# beechainuino.net
KiCad netlist of a schematic drawn in EAGLE
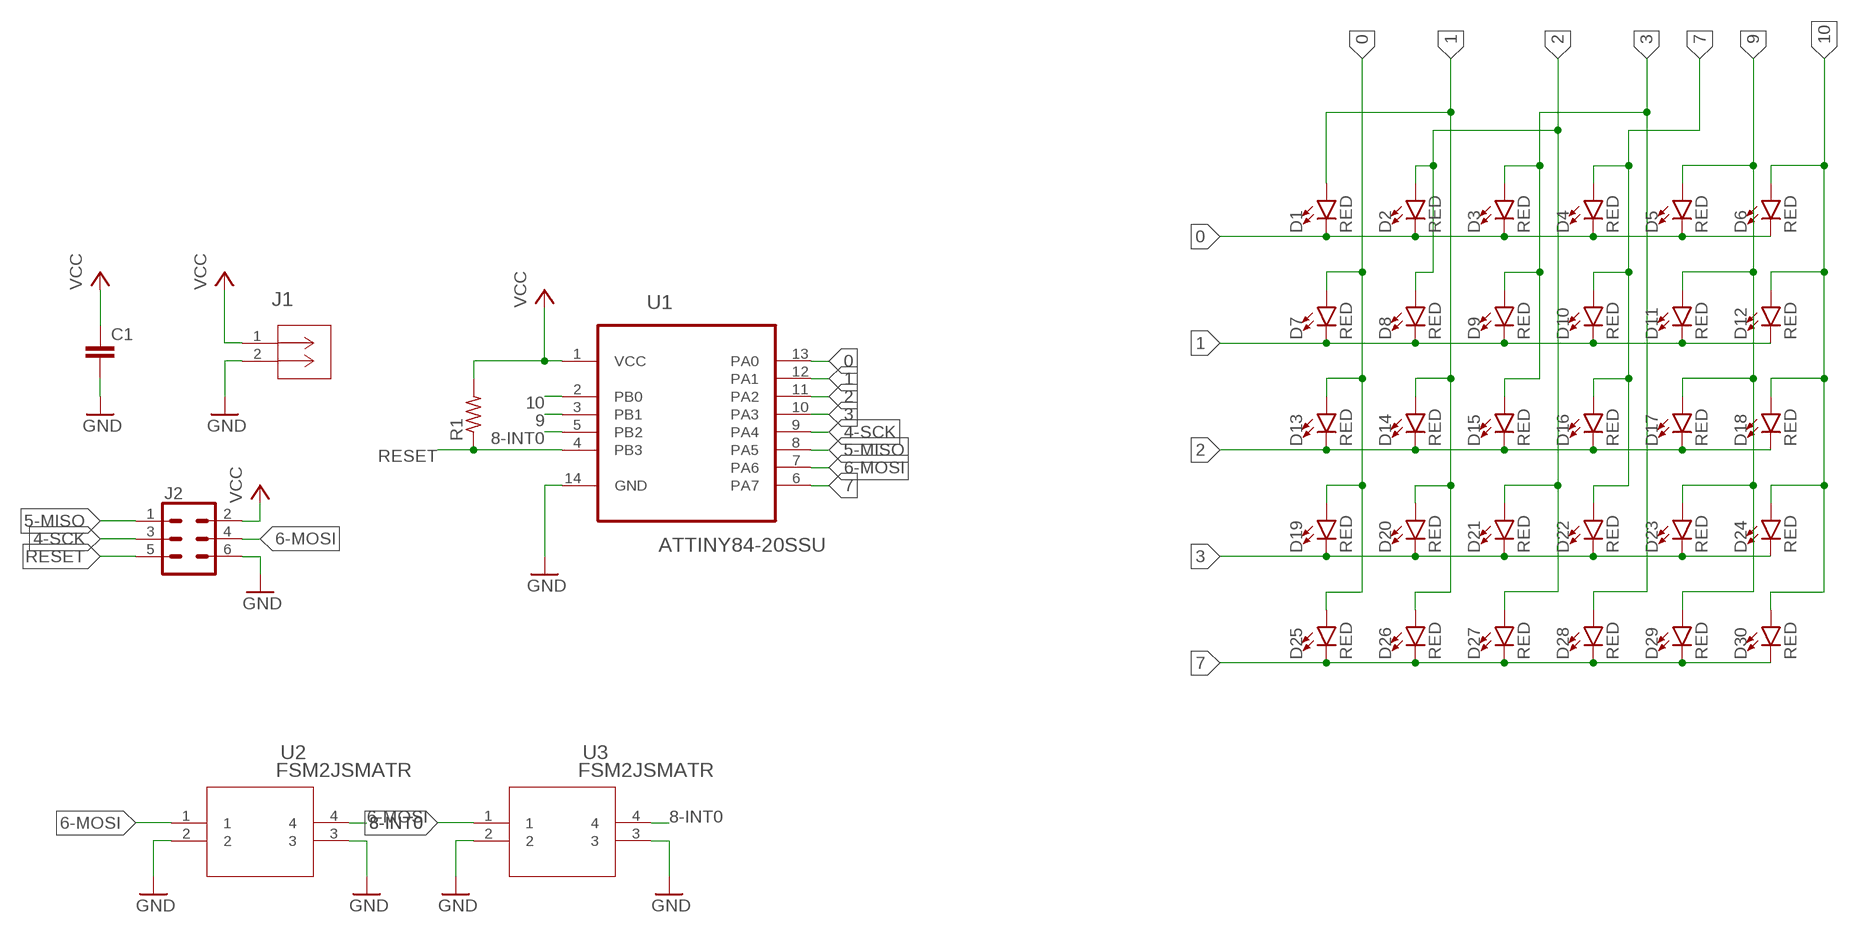
[diagram p0: schematic, sheet 1]

(export (version "E")
  (design (tool "Eeschema 10.0.6"))
  (components
    (comp (ref "C1")
      (value "C-EUC0603K")
      (footprint "eagle-import:C0603K")
      (libsource (lib "eagle-import") (part "C-EUC0603K"))
    )
    (comp (ref "D1")
      (value "RED")
      (footprint "eagle-import:LED-0603")
      (libsource (lib "eagle-import") (part "LED-RED0603"))
    )
    (comp (ref "D2")
      (value "RED")
      (footprint "eagle-import:LED-0603")
      (libsource (lib "eagle-import") (part "LED-RED0603"))
    )
    (comp (ref "D3")
      (value "RED")
      (footprint "eagle-import:LED-0603")
      (libsource (lib "eagle-import") (part "LED-RED0603"))
    )
    (comp (ref "D4")
      (value "RED")
      (footprint "eagle-import:LED-0603")
      (libsource (lib "eagle-import") (part "LED-RED0603"))
    )
    (comp (ref "D5")
      (value "RED")
      (footprint "eagle-import:LED-0603")
      (libsource (lib "eagle-import") (part "LED-RED0603"))
    )
    (comp (ref "D6")
      (value "RED")
      (footprint "eagle-import:LED-0603")
      (libsource (lib "eagle-import") (part "LED-RED0603"))
    )
    (comp (ref "D7")
      (value "RED")
      (footprint "eagle-import:LED-0603")
      (libsource (lib "eagle-import") (part "LED-RED0603"))
    )
    (comp (ref "D8")
      (value "RED")
      (footprint "eagle-import:LED-0603")
      (libsource (lib "eagle-import") (part "LED-RED0603"))
    )
    (comp (ref "D9")
      (value "RED")
      (footprint "eagle-import:LED-0603")
      (libsource (lib "eagle-import") (part "LED-RED0603"))
    )
    (comp (ref "D10")
      (value "RED")
      (footprint "eagle-import:LED-0603")
      (libsource (lib "eagle-import") (part "LED-RED0603"))
    )
    (comp (ref "D11")
      (value "RED")
      (footprint "eagle-import:LED-0603")
      (libsource (lib "eagle-import") (part "LED-RED0603"))
    )
    (comp (ref "D12")
      (value "RED")
      (footprint "eagle-import:LED-0603")
      (libsource (lib "eagle-import") (part "LED-RED0603"))
    )
    (comp (ref "D13")
      (value "RED")
      (footprint "eagle-import:LED-0603")
      (libsource (lib "eagle-import") (part "LED-RED0603"))
    )
    (comp (ref "D14")
      (value "RED")
      (footprint "eagle-import:LED-0603")
      (libsource (lib "eagle-import") (part "LED-RED0603"))
    )
    (comp (ref "D15")
      (value "RED")
      (footprint "eagle-import:LED-0603")
      (libsource (lib "eagle-import") (part "LED-RED0603"))
    )
    (comp (ref "D16")
      (value "RED")
      (footprint "eagle-import:LED-0603")
      (libsource (lib "eagle-import") (part "LED-RED0603"))
    )
    (comp (ref "D17")
      (value "RED")
      (footprint "eagle-import:LED-0603")
      (libsource (lib "eagle-import") (part "LED-RED0603"))
    )
    (comp (ref "D18")
      (value "RED")
      (footprint "eagle-import:LED-0603")
      (libsource (lib "eagle-import") (part "LED-RED0603"))
    )
    (comp (ref "D19")
      (value "RED")
      (footprint "eagle-import:LED-0603")
      (libsource (lib "eagle-import") (part "LED-RED0603"))
    )
    (comp (ref "D20")
      (value "RED")
      (footprint "eagle-import:LED-0603")
      (libsource (lib "eagle-import") (part "LED-RED0603"))
    )
    (comp (ref "D21")
      (value "RED")
      (footprint "eagle-import:LED-0603")
      (libsource (lib "eagle-import") (part "LED-RED0603"))
    )
    (comp (ref "D22")
      (value "RED")
      (footprint "eagle-import:LED-0603")
      (libsource (lib "eagle-import") (part "LED-RED0603"))
    )
    (comp (ref "D23")
      (value "RED")
      (footprint "eagle-import:LED-0603")
      (libsource (lib "eagle-import") (part "LED-RED0603"))
    )
    (comp (ref "D24")
      (value "RED")
      (footprint "eagle-import:LED-0603")
      (libsource (lib "eagle-import") (part "LED-RED0603"))
    )
    (comp (ref "D25")
      (value "RED")
      (footprint "eagle-import:LED-0603")
      (libsource (lib "eagle-import") (part "LED-RED0603"))
    )
    (comp (ref "D26")
      (value "RED")
      (footprint "eagle-import:LED-0603")
      (libsource (lib "eagle-import") (part "LED-RED0603"))
    )
    (comp (ref "D27")
      (value "RED")
      (footprint "eagle-import:LED-0603")
      (libsource (lib "eagle-import") (part "LED-RED0603"))
    )
    (comp (ref "D28")
      (value "RED")
      (footprint "eagle-import:LED-0603")
      (libsource (lib "eagle-import") (part "LED-RED0603"))
    )
    (comp (ref "D29")
      (value "RED")
      (footprint "eagle-import:LED-0603")
      (libsource (lib "eagle-import") (part "LED-RED0603"))
    )
    (comp (ref "D30")
      (value "RED")
      (footprint "eagle-import:LED-0603")
      (libsource (lib "eagle-import") (part "LED-RED0603"))
    )
    (comp (ref "J1")
      (value "796136-1")
      (footprint "eagle-import:CON2_BATT-HOLDER_SMT")
      (fields (field (name "MANUFACTURER_PART_NUMBER") "7961361"))
      (libsource (lib "eagle-import") (part "796136-1"))
    )
    (comp (ref "J2")
      (value "CONN_03X2FEMALE_SMD")
      (footprint "eagle-import:2X3_SMD")
      (libsource (lib "eagle-import") (part "CONN_03X2FEMALE_SMD"))
    )
    (comp (ref "R1")
      (value "R-US_R0603")
      (footprint "eagle-import:R0603")
      (libsource (lib "eagle-import") (part "R-US_R0603"))
    )
    (comp (ref "U1")
      (value "ATTINY84-20SSU")
      (footprint "eagle-import:SOIC127P600X175-14N")
      (libsource (lib "eagle-import") (part "ATTINY84-20SSU"))
    )
    (comp (ref "U2")
      (value "FSM2JSMATR")
      (footprint "eagle-import:SWITCH_FSM2JSMAA")
      (libsource (lib "eagle-import") (part "FSM2JSMATR"))
    )
    (comp (ref "U3")
      (value "FSM2JSMATR")
      (footprint "eagle-import:SWITCH_FSM2JSMAA")
      (libsource (lib "eagle-import") (part "FSM2JSMATR"))
    )
  )
  (nets
    (net (code "1") (name "0") (class "Default")
      (node (ref "D1") (pin "C") (pinfunction "C_C") (pintype "passive"))
      (node (ref "D13") (pin "A") (pinfunction "A_A") (pintype "passive"))
      (node (ref "D19") (pin "A") (pinfunction "A_A") (pintype "passive"))
      (node (ref "D2") (pin "C") (pinfunction "C_C") (pintype "passive"))
      (node (ref "D25") (pin "A") (pinfunction "A_A") (pintype "passive"))
      (node (ref "D3") (pin "C") (pinfunction "C_C") (pintype "passive"))
      (node (ref "D4") (pin "C") (pinfunction "C_C") (pintype "passive"))
      (node (ref "D5") (pin "C") (pinfunction "C_C") (pintype "passive"))
      (node (ref "D6") (pin "C") (pinfunction "C_C") (pintype "passive"))
      (node (ref "D7") (pin "A") (pinfunction "A_A") (pintype "passive"))
      (node (ref "U1") (pin "13") (pinfunction "PA0_13") (pintype "bidirectional"))
    )
    (net (code "2") (name "1") (class "Default")
      (node (ref "D1") (pin "A") (pinfunction "A_A") (pintype "passive"))
      (node (ref "D10") (pin "C") (pinfunction "C_C") (pintype "passive"))
      (node (ref "D11") (pin "C") (pinfunction "C_C") (pintype "passive"))
      (node (ref "D12") (pin "C") (pinfunction "C_C") (pintype "passive"))
      (node (ref "D14") (pin "A") (pinfunction "A_A") (pintype "passive"))
      (node (ref "D20") (pin "A") (pinfunction "A_A") (pintype "passive"))
      (node (ref "D26") (pin "A") (pinfunction "A_A") (pintype "passive"))
      (node (ref "D7") (pin "C") (pinfunction "C_C") (pintype "passive"))
      (node (ref "D8") (pin "C") (pinfunction "C_C") (pintype "passive"))
      (node (ref "D9") (pin "C") (pinfunction "C_C") (pintype "passive"))
      (node (ref "U1") (pin "12") (pinfunction "PA1_12") (pintype "bidirectional"))
    )
    (net (code "3") (name "2") (class "Default")
      (node (ref "D13") (pin "C") (pinfunction "C_C") (pintype "passive"))
      (node (ref "D14") (pin "C") (pinfunction "C_C") (pintype "passive"))
      (node (ref "D15") (pin "C") (pinfunction "C_C") (pintype "passive"))
      (node (ref "D16") (pin "C") (pinfunction "C_C") (pintype "passive"))
      (node (ref "D17") (pin "C") (pinfunction "C_C") (pintype "passive"))
      (node (ref "D18") (pin "C") (pinfunction "C_C") (pintype "passive"))
      (node (ref "D2") (pin "A") (pinfunction "A_A") (pintype "passive"))
      (node (ref "D21") (pin "A") (pinfunction "A_A") (pintype "passive"))
      (node (ref "D27") (pin "A") (pinfunction "A_A") (pintype "passive"))
      (node (ref "D8") (pin "A") (pinfunction "A_A") (pintype "passive"))
      (node (ref "U1") (pin "11") (pinfunction "PA2_11") (pintype "bidirectional"))
    )
    (net (code "4") (name "3") (class "Default")
      (node (ref "D15") (pin "A") (pinfunction "A_A") (pintype "passive"))
      (node (ref "D19") (pin "C") (pinfunction "C_C") (pintype "passive"))
      (node (ref "D20") (pin "C") (pinfunction "C_C") (pintype "passive"))
      (node (ref "D21") (pin "C") (pinfunction "C_C") (pintype "passive"))
      (node (ref "D22") (pin "C") (pinfunction "C_C") (pintype "passive"))
      (node (ref "D23") (pin "C") (pinfunction "C_C") (pintype "passive"))
      (node (ref "D24") (pin "C") (pinfunction "C_C") (pintype "passive"))
      (node (ref "D28") (pin "A") (pinfunction "A_A") (pintype "passive"))
      (node (ref "D3") (pin "A") (pinfunction "A_A") (pintype "passive"))
      (node (ref "D9") (pin "A") (pinfunction "A_A") (pintype "passive"))
      (node (ref "U1") (pin "10") (pinfunction "PA3_10") (pintype "bidirectional"))
    )
    (net (code "5") (name "4-SCK") (class "Default")
      (node (ref "J2") (pin "3") (pinfunction "3_3") (pintype "bidirectional"))
      (node (ref "U1") (pin "9") (pinfunction "PA4_9") (pintype "bidirectional"))
    )
    (net (code "6") (name "5-MISO") (class "Default")
      (node (ref "J2") (pin "1") (pinfunction "1_1") (pintype "bidirectional"))
      (node (ref "U1") (pin "8") (pinfunction "PA5_8") (pintype "bidirectional"))
    )
    (net (code "7") (name "6-MOSI") (class "Default")
      (node (ref "J2") (pin "4") (pinfunction "4_4") (pintype "bidirectional"))
      (node (ref "U1") (pin "7") (pinfunction "PA6_7") (pintype "bidirectional"))
      (node (ref "U2") (pin "1") (pinfunction "1_1") (pintype "passive"))
      (node (ref "U2") (pin "4") (pinfunction "4_4") (pintype "passive"))
    )
    (net (code "8") (name "7") (class "Default")
      (node (ref "D10") (pin "A") (pinfunction "A_A") (pintype "passive"))
      (node (ref "D16") (pin "A") (pinfunction "A_A") (pintype "passive"))
      (node (ref "D22") (pin "A") (pinfunction "A_A") (pintype "passive"))
      (node (ref "D25") (pin "C") (pinfunction "C_C") (pintype "passive"))
      (node (ref "D26") (pin "C") (pinfunction "C_C") (pintype "passive"))
      (node (ref "D27") (pin "C") (pinfunction "C_C") (pintype "passive"))
      (node (ref "D28") (pin "C") (pinfunction "C_C") (pintype "passive"))
      (node (ref "D29") (pin "C") (pinfunction "C_C") (pintype "passive"))
      (node (ref "D30") (pin "C") (pinfunction "C_C") (pintype "passive"))
      (node (ref "D4") (pin "A") (pinfunction "A_A") (pintype "passive"))
      (node (ref "U1") (pin "6") (pinfunction "PA7_6") (pintype "bidirectional"))
    )
    (net (code "9") (name "8-INT0") (class "Default")
      (node (ref "U1") (pin "5") (pinfunction "PB2_5") (pintype "bidirectional"))
      (node (ref "U3") (pin "1") (pinfunction "1_1") (pintype "passive"))
      (node (ref "U3") (pin "4") (pinfunction "4_4") (pintype "passive"))
    )
    (net (code "10") (name "9") (class "Default")
      (node (ref "D11") (pin "A") (pinfunction "A_A") (pintype "passive"))
      (node (ref "D17") (pin "A") (pinfunction "A_A") (pintype "passive"))
      (node (ref "D23") (pin "A") (pinfunction "A_A") (pintype "passive"))
      (node (ref "D29") (pin "A") (pinfunction "A_A") (pintype "passive"))
      (node (ref "D5") (pin "A") (pinfunction "A_A") (pintype "passive"))
      (node (ref "U1") (pin "3") (pinfunction "PB1_3") (pintype "bidirectional"))
    )
    (net (code "11") (name "10") (class "Default")
      (node (ref "D12") (pin "A") (pinfunction "A_A") (pintype "passive"))
      (node (ref "D18") (pin "A") (pinfunction "A_A") (pintype "passive"))
      (node (ref "D24") (pin "A") (pinfunction "A_A") (pintype "passive"))
      (node (ref "D30") (pin "A") (pinfunction "A_A") (pintype "passive"))
      (node (ref "D6") (pin "A") (pinfunction "A_A") (pintype "passive"))
      (node (ref "U1") (pin "2") (pinfunction "PB0_2") (pintype "bidirectional"))
    )
    (net (code "12") (name "GND") (class "Default")
      (node (ref "C1") (pin "2") (pinfunction "2_2") (pintype "passive"))
      (node (ref "J1") (pin "2") (pinfunction "2_2") (pintype "passive"))
      (node (ref "J2") (pin "6") (pinfunction "6_6") (pintype "bidirectional"))
      (node (ref "U1") (pin "14") (pinfunction "GND_14") (pintype "passive"))
      (node (ref "U2") (pin "2") (pinfunction "2_2") (pintype "passive"))
      (node (ref "U2") (pin "3") (pinfunction "3_3") (pintype "passive"))
      (node (ref "U3") (pin "2") (pinfunction "2_2") (pintype "passive"))
      (node (ref "U3") (pin "3") (pinfunction "3_3") (pintype "passive"))
    )
    (net (code "13") (name "RESET") (class "Default")
      (node (ref "J2") (pin "5") (pinfunction "5_5") (pintype "bidirectional"))
      (node (ref "R1") (pin "1") (pinfunction "1_1") (pintype "passive"))
      (node (ref "U1") (pin "4") (pinfunction "PB3_4") (pintype "bidirectional"))
    )
    (net (code "14") (name "VCC") (class "Default")
      (node (ref "C1") (pin "1") (pinfunction "1_1") (pintype "passive"))
      (node (ref "J1") (pin "1") (pinfunction "1_1") (pintype "passive"))
      (node (ref "J2") (pin "2") (pinfunction "2_2") (pintype "bidirectional"))
      (node (ref "R1") (pin "2") (pinfunction "2_2") (pintype "passive"))
      (node (ref "U1") (pin "1") (pinfunction "VCC_1") (pintype "power_in"))
    )
  )
)
